# 1-Schematic_Antenna_analyzer_SMD.net
KiCad netlist of a schematic drawn in EasyEDA
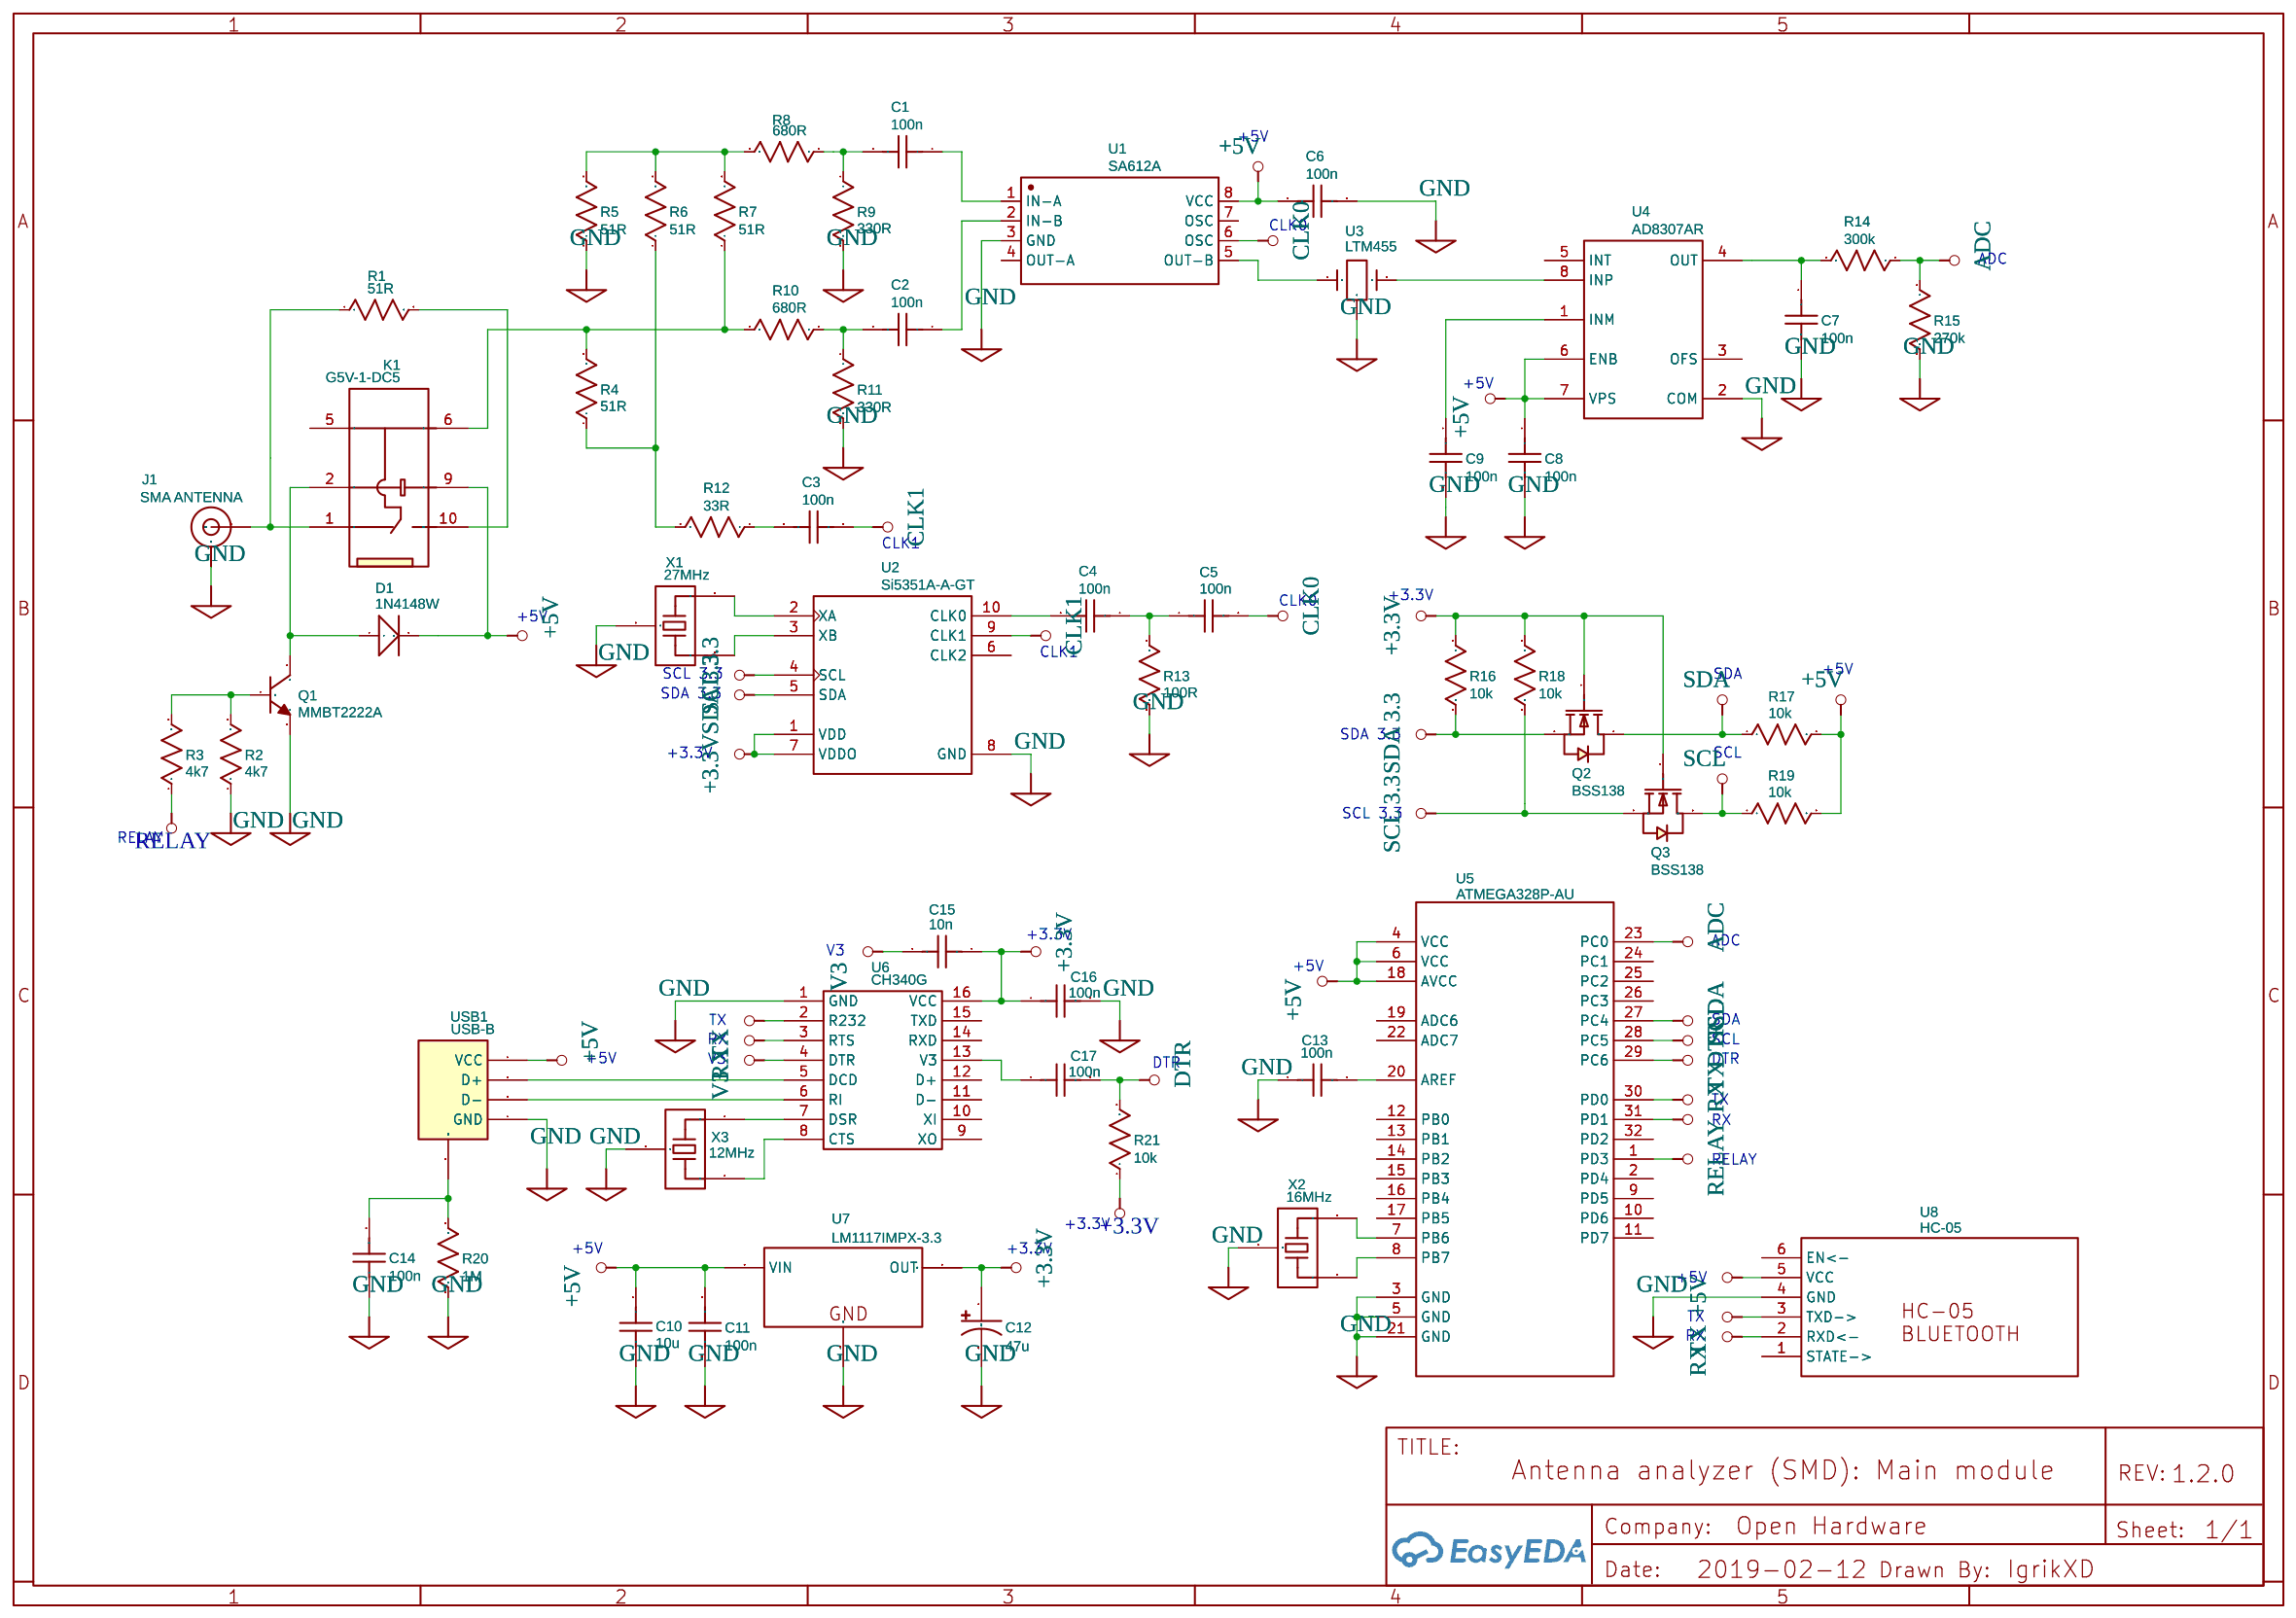
[diagram p0: schematic sheet]

(export (version "E")
  (design (tool "Eeschema 10.0.6"))
  (components
    (comp (ref "C1")
      (value "100n")
      (fields
        (field (name "BOM_Manufacturer Part") "CC0805JRX7R9BB104")
        (field (name "BOM_Supplier Part") "C111492")
      )
      (libsource (lib "") (part "Cap_0805_US_1"))
    )
    (comp (ref "C2")
      (value "100n")
      (fields
        (field (name "BOM_Manufacturer Part") "CC0805JRX7R9BB104")
        (field (name "BOM_Supplier Part") "C111492")
      )
      (libsource (lib "") (part "Cap_0805_US_1"))
    )
    (comp (ref "C3")
      (value "100n")
      (fields
        (field (name "BOM_Manufacturer Part") "CC0805JRX7R9BB104")
        (field (name "BOM_Supplier Part") "C111492")
      )
      (libsource (lib "") (part "Cap_0805_US_1"))
    )
    (comp (ref "C4")
      (value "100n")
      (fields
        (field (name "BOM_Manufacturer Part") "CC0805JRX7R9BB104")
        (field (name "BOM_Supplier Part") "C111492")
      )
      (libsource (lib "") (part "Cap_0805_US_1"))
    )
    (comp (ref "C5")
      (value "100n")
      (fields
        (field (name "BOM_Manufacturer Part") "CC0805JRX7R9BB104")
        (field (name "BOM_Supplier Part") "C111492")
      )
      (libsource (lib "") (part "Cap_0805_US"))
    )
    (comp (ref "C6")
      (value "100n")
      (fields
        (field (name "BOM_Manufacturer Part") "CC0805JRX7R9BB104")
        (field (name "BOM_Supplier Part") "C111492")
      )
      (libsource (lib "") (part "Cap_0805_US"))
    )
    (comp (ref "C7")
      (value "100n")
      (fields
        (field (name "BOM_Manufacturer Part") "CC0805JRX7R9BB104")
        (field (name "BOM_Supplier Part") "C111492")
      )
      (libsource (lib "") (part "Cap_0805_US_2"))
    )
    (comp (ref "C8")
      (value "100n")
      (fields
        (field (name "BOM_Manufacturer Part") "CC0805JRX7R9BB104")
        (field (name "BOM_Supplier Part") "C111492")
      )
      (libsource (lib "") (part "Cap_0805_US_2"))
    )
    (comp (ref "C9")
      (value "100n")
      (fields
        (field (name "BOM_Manufacturer Part") "CC0805JRX7R9BB104")
        (field (name "BOM_Supplier Part") "C111492")
      )
      (libsource (lib "") (part "Cap_0805_US_2"))
    )
    (comp (ref "C10")
      (value "10u")
      (fields
        (field (name "BOM_Manufacturer Part") "CL21A106KAYNNNE")
        (field (name "BOM_Supplier Part") "C15850")
      )
      (libsource (lib "") (part "Capacitor"))
    )
    (comp (ref "C11")
      (value "100n")
      (fields
        (field (name "BOM_Manufacturer Part") "CC0805JRX7R9BB104")
        (field (name "BOM_Supplier Part") "C111492")
      )
      (libsource (lib "") (part "Capacitor_1"))
    )
    (comp (ref "C12")
      (value "47u")
      (fields
        (field (name "BOM_Manufacturer Part") "TAJB476K010RNJ")
        (field (name "BOM_Supplier Part") "C22036")
      )
      (libsource (lib "") (part "Cap_Electrolytic(TH)_D3.0XF1.5_US"))
    )
    (comp (ref "C13")
      (value "100n")
      (fields
        (field (name "BOM_Manufacturer Part") "CC0805JRX7R9BB104")
        (field (name "BOM_Supplier Part") "C111492")
      )
      (libsource (lib "") (part "Cap_0805_US"))
    )
    (comp (ref "C14")
      (value "100n")
      (fields
        (field (name "BOM_Manufacturer Part") "CC0805JRX7R9BB104")
        (field (name "BOM_Supplier Part") "C111492")
      )
      (libsource (lib "") (part "Capacitor_1"))
    )
    (comp (ref "C15")
      (value "10n")
      (fields
        (field (name "BOM_Manufacturer Part") "0805B103J500NT")
        (field (name "BOM_Supplier Part") "C24666")
      )
      (libsource (lib "") (part "Cap_0805_US_1"))
    )
    (comp (ref "C16")
      (value "100n")
      (fields
        (field (name "BOM_Manufacturer Part") "CC0805JRX7R9BB104")
        (field (name "BOM_Supplier Part") "C111492")
      )
      (libsource (lib "") (part "Cap_0805_US"))
    )
    (comp (ref "C17")
      (value "100n")
      (fields
        (field (name "BOM_Manufacturer Part") "CC0805JRX7R9BB104")
        (field (name "BOM_Supplier Part") "C111492")
      )
      (libsource (lib "") (part "Cap_0805_US"))
    )
    (comp (ref "D1")
      (value "1N4148W")
      (fields (field (name "BOM_Supplier Part") "C129216"))
      (libsource (lib "") (part "Unknown_190_315"))
    )
    (comp (ref "J1")
      (value "SMA ANTENNA")
      (fields
        (field (name "BOM_Manufacturer Part") "ANKX01.0093")
        (field (name "BOM_Supplier Part") "C129604")
      )
      (libsource (lib "") (part "Unknown_105_280"))
    )
    (comp (ref "K1")
      (value "G5V-1-DC5")
      (fields (field (name "BOM_Supplier Part") "C152705"))
      (libsource (lib "") (part "Unknown_190_235"))
    )
    (comp (ref "Q1")
      (value "MMBT2222A")
      (fields (field (name "BOM_Supplier Part") "C83939"))
      (libsource (lib "") (part "Unknown_130_345"))
    )
    (comp (ref "Q2")
      (value "BSS138")
      (fields (field (name "BOM_Supplier Part") "C52895"))
      (libsource (lib "") (part "Unknown_795_355"))
    )
    (comp (ref "Q3")
      (value "BSS138")
      (fields (field (name "BOM_Supplier Part") "C52895"))
      (libsource (lib "") (part "Unknown_835_395"))
    )
    (comp (ref "R1")
      (value "51R")
      (fields
        (field (name "BOM_Manufacturer Part") "AR05BTCW0510")
        (field (name "BOM_Supplier Part") "C318143")
      )
      (libsource (lib "") (part "Res_0805(1/8W)_US_3"))
    )
    (comp (ref "R2")
      (value "4k7")
      (fields
        (field (name "BOM_Manufacturer Part") "MCR10EZPD4701")
        (field (name "BOM_Supplier Part") "C308367")
      )
      (libsource (lib "") (part "Res_0805(1/8W)_US_1"))
    )
    (comp (ref "R3")
      (value "4k7")
      (fields
        (field (name "BOM_Manufacturer Part") "MCR10EZPD4701")
        (field (name "BOM_Supplier Part") "C308367")
      )
      (libsource (lib "") (part "Res_0805(1/8W)_US_1"))
    )
    (comp (ref "R4")
      (value "51R")
      (fields
        (field (name "BOM_Manufacturer Part") "AR05BTCW0510")
        (field (name "BOM_Supplier Part") "C318143")
      )
      (libsource (lib "") (part "Res_0805(1/8W)_US_1"))
    )
    (comp (ref "R5")
      (value "51R")
      (fields
        (field (name "BOM_Manufacturer Part") "AR05BTCW0510")
        (field (name "BOM_Supplier Part") "C318143")
      )
      (libsource (lib "") (part "Res_0805(1/8W)_US_1"))
    )
    (comp (ref "R6")
      (value "51R")
      (fields
        (field (name "BOM_Manufacturer Part") "AR05BTCW0510")
        (field (name "BOM_Supplier Part") "C318143")
      )
      (libsource (lib "") (part "Res_0805(1/8W)_US_1"))
    )
    (comp (ref "R7")
      (value "51R")
      (fields
        (field (name "BOM_Manufacturer Part") "AR05BTCW0510")
        (field (name "BOM_Supplier Part") "C318143")
      )
      (libsource (lib "") (part "Res_0805(1/8W)_US_1"))
    )
    (comp (ref "R8")
      (value "680R")
      (fields
        (field (name "BOM_Manufacturer Part") "AR05BTCW6800")
        (field (name "BOM_Supplier Part") "C318149")
      )
      (libsource (lib "") (part "Res_0805(1/8W)_US_2"))
    )
    (comp (ref "R9")
      (value "330R")
      (fields
        (field (name "BOM_Manufacturer Part") "5-1614884-2")
        (field (name "BOM_Supplier Part") "C306269")
      )
      (libsource (lib "") (part "Res_0805(1/8W)_US"))
    )
    (comp (ref "R10")
      (value "680R")
      (fields
        (field (name "BOM_Manufacturer Part") "AR05BTCW6800")
        (field (name "BOM_Supplier Part") "C318149")
      )
      (libsource (lib "") (part "Res_0805(1/8W)_US_2"))
    )
    (comp (ref "R11")
      (value "330R")
      (fields
        (field (name "BOM_Manufacturer Part") "5-1614884-2")
        (field (name "BOM_Supplier Part") "C306269")
      )
      (libsource (lib "") (part "Res_0805(1/8W)_US"))
    )
    (comp (ref "R12")
      (value "33R")
      (fields
        (field (name "BOM_Manufacturer Part") "0805W8F330JT5E")
        (field (name "BOM_Supplier Part") "C17634")
      )
      (libsource (lib "") (part "Res_0805(1/8W)_US_2"))
    )
    (comp (ref "R13")
      (value "100R")
      (fields
        (field (name "BOM_Manufacturer Part") "RG2012P-101-B-T5")
        (field (name "BOM_Supplier Part") "C95679")
      )
      (libsource (lib "") (part "Res_0805(1/8W)_US"))
    )
    (comp (ref "R14")
      (value "300k")
      (fields
        (field (name "BOM_Manufacturer Part") "WR08X3003FTL")
        (field (name "BOM_Supplier Part") "C168438")
      )
      (libsource (lib "") (part "Res_0805(1/8W)_US_2"))
    )
    (comp (ref "R15")
      (value "270k")
      (fields
        (field (name "BOM_Manufacturer Part") "0805W8F2703T5E")
        (field (name "BOM_Supplier Part") "C17589")
      )
      (libsource (lib "") (part "Res_0805(1/8W)_US"))
    )
    (comp (ref "R16")
      (value "10k")
      (fields
        (field (name "BOM_Manufacturer Part") "0805WAD1002T5E")
        (field (name "BOM_Supplier Part") "C169071")
      )
      (libsource (lib "") (part "Res_0805(1/8W)_US"))
    )
    (comp (ref "R17")
      (value "10k")
      (fields
        (field (name "BOM_Manufacturer Part") "0805WAD1002T5E")
        (field (name "BOM_Supplier Part") "C169071")
      )
      (libsource (lib "") (part "Res_0805(1/8W)_US_3"))
    )
    (comp (ref "R18")
      (value "10k")
      (fields
        (field (name "BOM_Manufacturer Part") "0805WAD1002T5E")
        (field (name "BOM_Supplier Part") "C169071")
      )
      (libsource (lib "") (part "Res_0805(1/8W)_US"))
    )
    (comp (ref "R19")
      (value "10k")
      (fields
        (field (name "BOM_Manufacturer Part") "0805WAD1002T5E")
        (field (name "BOM_Supplier Part") "C169071")
      )
      (libsource (lib "") (part "Res_0805(1/8W)_US_3"))
    )
    (comp (ref "R20")
      (value "1M")
      (fields
        (field (name "BOM_Manufacturer Part") "RC0805FR-071ML")
        (field (name "BOM_Supplier Part") "C107700")
      )
      (libsource (lib "") (part "Resistor"))
    )
    (comp (ref "R21")
      (value "10k")
      (fields
        (field (name "BOM_Manufacturer Part") "0805WAD1002T5E")
        (field (name "BOM_Supplier Part") "C169071")
      )
      (libsource (lib "") (part "Resistor"))
    )
    (comp (ref "U1") (value "SA612A") (libsource (lib "") (part "Unknown_560_110")))
    (comp (ref "U2") (value "Si5351A-A-GT") (libsource (lib "") (part "Unknown_445_340")))
    (comp (ref "U3") (value "LTM455") (libsource (lib "") (part "Unknown_680_135")))
    (comp (ref "U4") (value "AD8307AR") (libsource (lib "") (part "Unknown_825_160")))
    (comp (ref "U5")
      (value "ATMEGA328P-AU")
      (fields (field (name "BOM_Supplier Part") "C14877"))
      (libsource (lib "") (part "Unknown_760_570"))
    )
    (comp (ref "U6")
      (value "CH340G")
      (fields (field (name "BOM_Supplier Part") "C14267"))
      (libsource (lib "") (part "Unknown_440_530"))
    )
    (comp (ref "U7")
      (value "LM1117IMPX-3.3")
      (fields
        (field (name "BOM_Manufacturer Part") "LM1117IMPX-3.3/NOPB")
        (field (name "BOM_Supplier Part") "C23984")
      )
      (libsource (lib "") (part "Unknown_420_645"))
    )
    (comp (ref "U8") (value "HC-05") (libsource (lib "") (part "Unknown_885_690")))
    (comp (ref "USB1")
      (value "USB-B")
      (fields
        (field (name "BOM_Manufacturer Part") "USB BFemale90 White plastic")
        (field (name "BOM_Supplier Part") "C46393")
      )
      (libsource (lib "") (part "Unknown_220_540"))
    )
    (comp (ref "X1")
      (value "27MHz")
      (fields
        (field (name "BOM_Manufacturer Part") "X3S027000BA1H-U")
        (field (name "BOM_Supplier Part") "C136079")
      )
      (libsource (lib "") (part "CSTCE16M0V53-R0"))
    )
    (comp (ref "X2")
      (value "16MHz")
      (fields
        (field (name "BOM_Manufacturer Part") "CSTCE16M0V53-R0")
        (field (name "BOM_Supplier Part") "C32180")
      )
      (libsource (lib "") (part "CSTCE16M0V53-R0"))
    )
    (comp (ref "X3")
      (value "12MHz")
      (fields
        (field (name "BOM_Manufacturer Part") "CSTCE12M0G52-R0")
        (field (name "BOM_Supplier Part") "C91580")
      )
      (libsource (lib "") (part "CSTCE16M0V53-R0"))
    )
  )
  (nets
    (net (code "1") (name "+3.3V") (class "Default")
      (node (ref "C12") (pin "1") (pinfunction "1_1") (pintype "unspecified"))
      (node (ref "C15") (pin "1") (pinfunction "1_1") (pintype "unspecified"))
      (node (ref "C16") (pin "1") (pinfunction "1_1") (pintype "unspecified"))
      (node (ref "Q2") (pin "1") (pinfunction "G_1") (pintype "unspecified"))
      (node (ref "Q3") (pin "1") (pinfunction "G_1") (pintype "unspecified"))
      (node (ref "R16") (pin "1") (pinfunction "1_1") (pintype "unspecified"))
      (node (ref "R18") (pin "1") (pinfunction "1_1") (pintype "unspecified"))
      (node (ref "R21") (pin "1") (pinfunction "1_1") (pintype "unspecified"))
      (node (ref "U2") (pin "1") (pinfunction "VDD_1") (pintype "passive"))
      (node (ref "U2") (pin "7") (pinfunction "VDDO_7") (pintype "passive"))
      (node (ref "U6") (pin "16") (pinfunction "VCC_16") (pintype "unspecified"))
      (node (ref "U7") (pin "2") (pinfunction "OUT_2") (pintype "unspecified"))
      (node (ref "U7") (pin "4") (pinfunction "OUT_4") (pintype "unspecified"))
    )
    (net (code "2") (name "+5V") (class "Default")
      (node (ref "C10") (pin "1") (pinfunction "1_1") (pintype "unspecified"))
      (node (ref "C11") (pin "2") (pinfunction "2_2") (pintype "unspecified"))
      (node (ref "C6") (pin "1") (pinfunction "1_1") (pintype "unspecified"))
      (node (ref "C8") (pin "1") (pinfunction "1_1") (pintype "unspecified"))
      (node (ref "D1") (pin "2") (pinfunction "C_2") (pintype "unspecified"))
      (node (ref "K1") (pin "9") (pinfunction "9_9") (pintype "input"))
      (node (ref "R17") (pin "2") (pinfunction "2_2") (pintype "unspecified"))
      (node (ref "R19") (pin "2") (pinfunction "2_2") (pintype "unspecified"))
      (node (ref "U1") (pin "8") (pinfunction "VCC_8") (pintype "unspecified"))
      (node (ref "U4") (pin "6") (pinfunction "ENB_6") (pintype "unspecified"))
      (node (ref "U4") (pin "7") (pinfunction "VPS_7") (pintype "passive"))
      (node (ref "U5") (pin "18") (pinfunction "AVCC_18") (pintype "passive"))
      (node (ref "U5") (pin "4") (pinfunction "VCC_4") (pintype "passive"))
      (node (ref "U5") (pin "6") (pinfunction "VCC_6") (pintype "passive"))
      (node (ref "U7") (pin "3") (pinfunction "VIN_3") (pintype "unspecified"))
      (node (ref "U8") (pin "5") (pinfunction "VCC_5") (pintype "unspecified"))
      (node (ref "USB1") (pin "1") (pinfunction "VCC_1") (pintype "input"))
    )
    (net (code "3") (name "ADC") (class "Default")
      (node (ref "R14") (pin "1") (pinfunction "1_1") (pintype "unspecified"))
      (node (ref "R15") (pin "1") (pinfunction "1_1") (pintype "unspecified"))
      (node (ref "U5") (pin "23") (pinfunction "PC0_23") (pintype "unspecified"))
    )
    (net (code "4") (name "CLK0") (class "Default")
      (node (ref "C5") (pin "2") (pinfunction "2_2") (pintype "unspecified"))
      (node (ref "U1") (pin "6") (pinfunction "OSC_6") (pintype "unspecified"))
    )
    (net (code "5") (name "CLK1") (class "Default")
      (node (ref "C3") (pin "1") (pinfunction "1_1") (pintype "unspecified"))
      (node (ref "U2") (pin "9") (pinfunction "CLK1_9") (pintype "unspecified"))
    )
    (net (code "6") (name "DTR") (class "Default")
      (node (ref "C17") (pin "2") (pinfunction "2_2") (pintype "unspecified"))
      (node (ref "R21") (pin "2") (pinfunction "2_2") (pintype "unspecified"))
      (node (ref "U5") (pin "29") (pinfunction "PC6_29") (pintype "unspecified"))
    )
    (net (code "7") (name "GND") (class "Default")
      (node (ref "C10") (pin "2") (pinfunction "2_2") (pintype "unspecified"))
      (node (ref "C11") (pin "1") (pinfunction "1_1") (pintype "unspecified"))
      (node (ref "C12") (pin "2") (pinfunction "2_2") (pintype "unspecified"))
      (node (ref "C13") (pin "1") (pinfunction "1_1") (pintype "unspecified"))
      (node (ref "C14") (pin "1") (pinfunction "1_1") (pintype "unspecified"))
      (node (ref "C16") (pin "2") (pinfunction "2_2") (pintype "unspecified"))
      (node (ref "C6") (pin "2") (pinfunction "2_2") (pintype "unspecified"))
      (node (ref "C7") (pin "2") (pinfunction "2_2") (pintype "unspecified"))
      (node (ref "C8") (pin "2") (pinfunction "2_2") (pintype "unspecified"))
      (node (ref "C9") (pin "2") (pinfunction "2_2") (pintype "unspecified"))
      (node (ref "J1") (pin "GND@0") (pinfunction "GND_GND@0") (pintype "unspecified"))
      (node (ref "J1") (pin "GND@1") (pinfunction "GND_GND@1") (pintype "unspecified"))
      (node (ref "J1") (pin "GND@2") (pinfunction "GND_GND@2") (pintype "unspecified"))
      (node (ref "J1") (pin "GND@3") (pinfunction "GND_GND@3") (pintype "unspecified"))
      (node (ref "Q1") (pin "2") (pinfunction "E_2") (pintype "unspecified"))
      (node (ref "R11") (pin "2") (pinfunction "2_2") (pintype "unspecified"))
      (node (ref "R13") (pin "2") (pinfunction "2_2") (pintype "unspecified"))
      (node (ref "R15") (pin "2") (pinfunction "2_2") (pintype "unspecified"))
      (node (ref "R2") (pin "1") (pinfunction "1_1") (pintype "unspecified"))
      (node (ref "R20") (pin "1") (pinfunction "1_1") (pintype "unspecified"))
      (node (ref "R5") (pin "1") (pinfunction "1_1") (pintype "unspecified"))
      (node (ref "R9") (pin "2") (pinfunction "2_2") (pintype "unspecified"))
      (node (ref "U1") (pin "3") (pinfunction "GND_3") (pintype "unspecified"))
      (node (ref "U2") (pin "8") (pinfunction "GND_8") (pintype "passive"))
      (node (ref "U3") (pin "3") (pinfunction "3_3") (pintype "unspecified"))
      (node (ref "U4") (pin "2") (pinfunction "COM_2") (pintype "passive"))
      (node (ref "U5") (pin "21") (pinfunction "GND_21") (pintype "unspecified"))
      (node (ref "U5") (pin "3") (pinfunction "GND_3") (pintype "unspecified"))
      (node (ref "U5") (pin "5") (pinfunction "GND_5") (pintype "unspecified"))
      (node (ref "U6") (pin "1") (pinfunction "GND_1") (pintype "unspecified"))
      (node (ref "U7") (pin "1") (pinfunction "ADJ_1") (pintype "unspecified"))
      (node (ref "U8") (pin "4") (pinfunction "GND_4") (pintype "unspecified"))
      (node (ref "USB1") (pin "4") (pinfunction "GND_4") (pintype "input"))
      (node (ref "X1") (pin "2") (pinfunction "2_2") (pintype "unspecified"))
      (node (ref "X2") (pin "2") (pinfunction "2_2") (pintype "unspecified"))
      (node (ref "X3") (pin "2") (pinfunction "2_2") (pintype "unspecified"))
    )
    (net (code "8") (name "Net-(C1-Pad2)") (class "Default")
      (node (ref "C1") (pin "2") (pinfunction "2_2") (pintype "unspecified"))
      (node (ref "R8") (pin "1") (pinfunction "1_1") (pintype "unspecified"))
      (node (ref "R9") (pin "1") (pinfunction "1_1") (pintype "unspecified"))
    )
    (net (code "9") (name "Net-(C2-Pad2)") (class "Default")
      (node (ref "C2") (pin "2") (pinfunction "2_2") (pintype "unspecified"))
      (node (ref "R10") (pin "1") (pinfunction "1_1") (pintype "unspecified"))
      (node (ref "R11") (pin "1") (pinfunction "1_1") (pintype "unspecified"))
    )
    (net (code "10") (name "Net-(C3-Pad2)") (class "Default")
      (node (ref "C3") (pin "2") (pinfunction "2_2") (pintype "unspecified"))
      (node (ref "R12") (pin "1") (pinfunction "1_1") (pintype "unspecified"))
    )
    (net (code "11") (name "Net-(C4-Pad1)") (class "Default")
      (node (ref "C4") (pin "1") (pinfunction "1_1") (pintype "unspecified"))
      (node (ref "C5") (pin "1") (pinfunction "1_1") (pintype "unspecified"))
      (node (ref "R13") (pin "1") (pinfunction "1_1") (pintype "unspecified"))
    )
    (net (code "12") (name "Net-(D1-A)") (class "Default")
      (node (ref "D1") (pin "1") (pinfunction "A_1") (pintype "unspecified"))
      (node (ref "K1") (pin "2") (pinfunction "2_2") (pintype "input"))
      (node (ref "Q1") (pin "3") (pinfunction "C_3") (pintype "unspecified"))
    )
    (net (code "13") (name "Net-(J1-SIGNAL)") (class "Default")
      (node (ref "J1") (pin "SIG") (pinfunction "SIGNAL_SIG") (pintype "unspecified"))
      (node (ref "K1") (pin "1") (pinfunction "1_1") (pintype "input"))
      (node (ref "R1") (pin "1") (pinfunction "1_1") (pintype "unspecified"))
    )
    (net (code "14") (name "Net-(K1-Pad6)") (class "Default")
      (node (ref "K1") (pin "6") (pinfunction "6_6") (pintype "input"))
      (node (ref "R10") (pin "2") (pinfunction "2_2") (pintype "unspecified"))
      (node (ref "R4") (pin "2") (pinfunction "2_2") (pintype "unspecified"))
      (node (ref "R7") (pin "1") (pinfunction "1_1") (pintype "unspecified"))
    )
    (net (code "15") (name "Net-(K1-Pad10)") (class "Default")
      (node (ref "K1") (pin "10") (pinfunction "10_10") (pintype "input"))
      (node (ref "R1") (pin "2") (pinfunction "2_2") (pintype "unspecified"))
    )
    (net (code "16") (name "Net-(Q1-B)") (class "Default")
      (node (ref "Q1") (pin "1") (pinfunction "B_1") (pintype "unspecified"))
      (node (ref "R2") (pin "2") (pinfunction "2_2") (pintype "unspecified"))
      (node (ref "R3") (pin "2") (pinfunction "2_2") (pintype "unspecified"))
    )
    (net (code "17") (name "Net-(R5-Pad2)") (class "Default")
      (node (ref "R5") (pin "2") (pinfunction "2_2") (pintype "unspecified"))
      (node (ref "R6") (pin "2") (pinfunction "2_2") (pintype "unspecified"))
      (node (ref "R7") (pin "2") (pinfunction "2_2") (pintype "unspecified"))
      (node (ref "R8") (pin "2") (pinfunction "2_2") (pintype "unspecified"))
    )
    (net (code "18") (name "Net-(R12-Pad2)") (class "Default")
      (node (ref "R12") (pin "2") (pinfunction "2_2") (pintype "unspecified"))
      (node (ref "R4") (pin "1") (pinfunction "1_1") (pintype "unspecified"))
      (node (ref "R6") (pin "1") (pinfunction "1_1") (pintype "unspecified"))
    )
    (net (code "19") (name "Net-(U1-IN-A)") (class "Default")
      (node (ref "C1") (pin "1") (pinfunction "1_1") (pintype "unspecified"))
      (node (ref "U1") (pin "1") (pinfunction "IN-A_1") (pintype "unspecified"))
    )
    (net (code "20") (name "Net-(U1-IN-B)") (class "Default")
      (node (ref "C2") (pin "1") (pinfunction "1_1") (pintype "unspecified"))
      (node (ref "U1") (pin "2") (pinfunction "IN-B_2") (pintype "unspecified"))
    )
    (net (code "21") (name "Net-(U1-OUT-B)") (class "Default")
      (node (ref "U1") (pin "5") (pinfunction "OUT-B_5") (pintype "unspecified"))
      (node (ref "U3") (pin "1") (pinfunction "1_1") (pintype "unspecified"))
    )
    (net (code "22") (name "Net-(U2-CLK0)") (class "Default")
      (node (ref "C4") (pin "2") (pinfunction "2_2") (pintype "unspecified"))
      (node (ref "U2") (pin "10") (pinfunction "CLK0_10") (pintype "unspecified"))
    )
    (net (code "23") (name "Net-(U2-XA)") (class "Default")
      (node (ref "U2") (pin "2") (pinfunction "XA_2") (pintype "unspecified"))
      (node (ref "X1") (pin "3") (pinfunction "3_3") (pintype "unspecified"))
    )
    (net (code "24") (name "Net-(U2-XB)") (class "Default")
      (node (ref "U2") (pin "3") (pinfunction "XB_3") (pintype "unspecified"))
      (node (ref "X1") (pin "1") (pinfunction "1_1") (pintype "unspecified"))
    )
    (net (code "25") (name "Net-(U4-INM)") (class "Default")
      (node (ref "C9") (pin "1") (pinfunction "1_1") (pintype "unspecified"))
      (node (ref "U4") (pin "1") (pinfunction "INM_1") (pintype "unspecified"))
    )
    (net (code "26") (name "Net-(U4-INP)") (class "Default")
      (node (ref "U3") (pin "2") (pinfunction "2_2") (pintype "unspecified"))
      (node (ref "U4") (pin "8") (pinfunction "INP_8") (pintype "unspecified"))
    )
    (net (code "27") (name "Net-(U4-OUT)") (class "Default")
      (node (ref "C7") (pin "1") (pinfunction "1_1") (pintype "unspecified"))
      (node (ref "R14") (pin "2") (pinfunction "2_2") (pintype "unspecified"))
      (node (ref "U4") (pin "4") (pinfunction "OUT_4") (pintype "output"))
    )
    (net (code "28") (name "Net-(U5-AREF)") (class "Default")
      (node (ref "C13") (pin "2") (pinfunction "2_2") (pintype "unspecified"))
      (node (ref "U5") (pin "20") (pinfunction "AREF_20") (pintype "input"))
    )
    (net (code "29") (name "Net-(U5-PB6)") (class "Default")
      (node (ref "U5") (pin "7") (pinfunction "PB6_7") (pintype "unspecified"))
      (node (ref "X2") (pin "3") (pinfunction "3_3") (pintype "unspecified"))
    )
    (net (code "30") (name "Net-(U5-PB7)") (class "Default")
      (node (ref "U5") (pin "8") (pinfunction "PB7_8") (pintype "unspecified"))
      (node (ref "X2") (pin "1") (pinfunction "1_1") (pintype "unspecified"))
    )
    (net (code "31") (name "Net-(U6-CTS)") (class "Default")
      (node (ref "U6") (pin "8") (pinfunction "CTS_8") (pintype "unspecified"))
      (node (ref "X3") (pin "1") (pinfunction "1_1") (pintype "unspecified"))
    )
    (net (code "32") (name "Net-(U6-DCD)") (class "Default")
      (node (ref "U6") (pin "5") (pinfunction "DCD_5") (pintype "unspecified"))
      (node (ref "USB1") (pin "3") (pinfunction "D+_3") (pintype "input"))
    )
    (net (code "33") (name "Net-(U6-DSR)") (class "Default")
      (node (ref "U6") (pin "7") (pinfunction "DSR_7") (pintype "unspecified"))
      (node (ref "X3") (pin "3") (pinfunction "3_3") (pintype "unspecified"))
    )
    (net (code "34") (name "Net-(U6-RI)") (class "Default")
      (node (ref "U6") (pin "6") (pinfunction "RI_6") (pintype "unspecified"))
      (node (ref "USB1") (pin "2") (pinfunction "D-_2") (pintype "input"))
    )
    (net (code "35") (name "Net-(U6-V3)") (class "Default")
      (node (ref "C17") (pin "1") (pinfunction "1_1") (pintype "unspecified"))
      (node (ref "U6") (pin "13") (pinfunction "V3_13") (pintype "unspecified"))
    )
    (net (code "36") (name "Net-(USB1-CASE)") (class "Default")
      (node (ref "C14") (pin "2") (pinfunction "2_2") (pintype "unspecified"))
      (node (ref "R20") (pin "2") (pinfunction "2_2") (pintype "unspecified"))
      (node (ref "USB1") (pin "5") (pinfunction "CASE_5") (pintype "unspecified"))
    )
    (net (code "37") (name "RELAY") (class "Default")
      (node (ref "R3") (pin "1") (pinfunction "1_1") (pintype "unspecified"))
      (node (ref "U5") (pin "1") (pinfunction "PD3_1") (pintype "unspecified"))
    )
    (net (code "38") (name "RX") (class "Default")
      (node (ref "U5") (pin "31") (pinfunction "PD1_31") (pintype "unspecified"))
      (node (ref "U6") (pin "3") (pinfunction "RTS_3") (pintype "unspecified"))
      (node (ref "U8") (pin "2") (pinfunction "RXD<-_2") (pintype "unspecified"))
    )
    (net (code "39") (name "SCL") (class "Default")
      (node (ref "Q3") (pin "3") (pinfunction "D_3") (pintype "unspecified"))
      (node (ref "R19") (pin "1") (pinfunction "1_1") (pintype "unspecified"))
      (node (ref "U5") (pin "28") (pinfunction "PC5_28") (pintype "unspecified"))
    )
    (net (code "40") (name "SCL 3.3") (class "Default")
      (node (ref "Q3") (pin "2") (pinfunction "S_2") (pintype "unspecified"))
      (node (ref "R18") (pin "2") (pinfunction "2_2") (pintype "unspecified"))
      (node (ref "U2") (pin "4") (pinfunction "SCL_4") (pintype "unspecified"))
    )
    (net (code "41") (name "SDA") (class "Default")
      (node (ref "Q2") (pin "3") (pinfunction "D_3") (pintype "unspecified"))
      (node (ref "R17") (pin "1") (pinfunction "1_1") (pintype "unspecified"))
      (node (ref "U5") (pin "27") (pinfunction "PC4_27") (pintype "unspecified"))
    )
    (net (code "42") (name "SDA 3.3") (class "Default")
      (node (ref "Q2") (pin "2") (pinfunction "S_2") (pintype "unspecified"))
      (node (ref "R16") (pin "2") (pinfunction "2_2") (pintype "unspecified"))
      (node (ref "U2") (pin "5") (pinfunction "SDA_5") (pintype "bidirectional"))
    )
    (net (code "43") (name "TX") (class "Default")
      (node (ref "U5") (pin "30") (pinfunction "PD0_30") (pintype "unspecified"))
      (node (ref "U6") (pin "2") (pinfunction "R232_2") (pintype "unspecified"))
      (node (ref "U8") (pin "3") (pinfunction "TXD->_3") (pintype "unspecified"))
    )
    (net (code "44") (name "V3") (class "Default")
      (node (ref "C15") (pin "2") (pinfunction "2_2") (pintype "unspecified"))
      (node (ref "U6") (pin "4") (pinfunction "DTR_4") (pintype "unspecified"))
    )
    (net (code "45") (name "unconnected-(K1-Pad5)") (class "Default")
      (node (ref "K1") (pin "5") (pinfunction "5_5") (pintype "input"))
    )
    (net (code "46") (name "unconnected-(U1-OSC-Pad7)") (class "Default")
      (node (ref "U1") (pin "7") (pinfunction "OSC_7") (pintype "unspecified"))
    )
    (net (code "47") (name "unconnected-(U1-OUT-A-Pad4)") (class "Default")
      (node (ref "U1") (pin "4") (pinfunction "OUT-A_4") (pintype "unspecified"))
    )
    (net (code "48") (name "unconnected-(U2-CLK2-Pad6)") (class "Default")
      (node (ref "U2") (pin "6") (pinfunction "CLK2_6") (pintype "unspecified"))
    )
    (net (code "49") (name "unconnected-(U4-INT-Pad5)") (class "Default")
      (node (ref "U4") (pin "5") (pinfunction "INT_5") (pintype "unspecified"))
    )
    (net (code "50") (name "unconnected-(U4-OFS-Pad3)") (class "Default")
      (node (ref "U4") (pin "3") (pinfunction "OFS_3") (pintype "unspecified"))
    )
    (net (code "51") (name "unconnected-(U5-ADC6-Pad19)") (class "Default")
      (node (ref "U5") (pin "19") (pinfunction "ADC6_19") (pintype "input"))
    )
    (net (code "52") (name "unconnected-(U5-ADC7-Pad22)") (class "Default")
      (node (ref "U5") (pin "22") (pinfunction "ADC7_22") (pintype "input"))
    )
    (net (code "53") (name "unconnected-(U5-PB0-Pad12)") (class "Default")
      (node (ref "U5") (pin "12") (pinfunction "PB0_12") (pintype "unspecified"))
    )
    (net (code "54") (name "unconnected-(U5-PB1-Pad13)") (class "Default")
      (node (ref "U5") (pin "13") (pinfunction "PB1_13") (pintype "unspecified"))
    )
    (net (code "55") (name "unconnected-(U5-PB2-Pad14)") (class "Default")
      (node (ref "U5") (pin "14") (pinfunction "PB2_14") (pintype "unspecified"))
    )
    (net (code "56") (name "unconnected-(U5-PB3-Pad15)") (class "Default")
      (node (ref "U5") (pin "15") (pinfunction "PB3_15") (pintype "unspecified"))
    )
    (net (code "57") (name "unconnected-(U5-PB4-Pad16)") (class "Default")
      (node (ref "U5") (pin "16") (pinfunction "PB4_16") (pintype "unspecified"))
    )
    (net (code "58") (name "unconnected-(U5-PB5-Pad17)") (class "Default")
      (node (ref "U5") (pin "17") (pinfunction "PB5_17") (pintype "unspecified"))
    )
    (net (code "59") (name "unconnected-(U5-PC1-Pad24)") (class "Default")
      (node (ref "U5") (pin "24") (pinfunction "PC1_24") (pintype "unspecified"))
    )
    (net (code "60") (name "unconnected-(U5-PC2-Pad25)") (class "Default")
      (node (ref "U5") (pin "25") (pinfunction "PC2_25") (pintype "unspecified"))
    )
    (net (code "61") (name "unconnected-(U5-PC3-Pad26)") (class "Default")
      (node (ref "U5") (pin "26") (pinfunction "PC3_26") (pintype "unspecified"))
    )
    (net (code "62") (name "unconnected-(U5-PD2-Pad32)") (class "Default")
      (node (ref "U5") (pin "32") (pinfunction "PD2_32") (pintype "unspecified"))
    )
    (net (code "63") (name "unconnected-(U5-PD4-Pad2)") (class "Default")
      (node (ref "U5") (pin "2") (pinfunction "PD4_2") (pintype "unspecified"))
    )
    (net (code "64") (name "unconnected-(U5-PD5-Pad9)") (class "Default")
      (node (ref "U5") (pin "9") (pinfunction "PD5_9") (pintype "unspecified"))
    )
    (net (code "65") (name "unconnected-(U5-PD6-Pad10)") (class "Default")
      (node (ref "U5") (pin "10") (pinfunction "PD6_10") (pintype "unspecified"))
    )
    (net (code "66") (name "unconnected-(U5-PD7-Pad11)") (class "Default")
      (node (ref "U5") (pin "11") (pinfunction "PD7_11") (pintype "unspecified"))
    )
    (net (code "67") (name "unconnected-(U6-D+-Pad12)") (class "Default")
      (node (ref "U6") (pin "12") (pinfunction "D+_12") (pintype "unspecified"))
    )
    (net (code "68") (name "unconnected-(U6-D--Pad11)") (class "Default")
      (node (ref "U6") (pin "11") (pinfunction "D-_11") (pintype "unspecified"))
    )
    (net (code "69") (name "unconnected-(U6-RXD-Pad14)") (class "Default")
      (node (ref "U6") (pin "14") (pinfunction "RXD_14") (pintype "unspecified"))
    )
    (net (code "70") (name "unconnected-(U6-TXD-Pad15)") (class "Default")
      (node (ref "U6") (pin "15") (pinfunction "TXD_15") (pintype "unspecified"))
    )
    (net (code "71") (name "unconnected-(U6-XI-Pad10)") (class "Default")
      (node (ref "U6") (pin "10") (pinfunction "XI_10") (pintype "unspecified"))
    )
    (net (code "72") (name "unconnected-(U6-XO-Pad9)") (class "Default")
      (node (ref "U6") (pin "9") (pinfunction "XO_9") (pintype "unspecified"))
    )
    (net (code "73") (name "unconnected-(U8-EN<--Pad6)") (class "Default")
      (node (ref "U8") (pin "6") (pinfunction "EN<-_6") (pintype "unspecified"))
    )
    (net (code "74") (name "unconnected-(U8-STATE->-Pad1)") (class "Default")
      (node (ref "U8") (pin "1") (pinfunction "STATE->_1") (pintype "unspecified"))
    )
  )
)
